# BitBeacon_Type_01.net
KiCad netlist of a schematic drawn in EAGLE
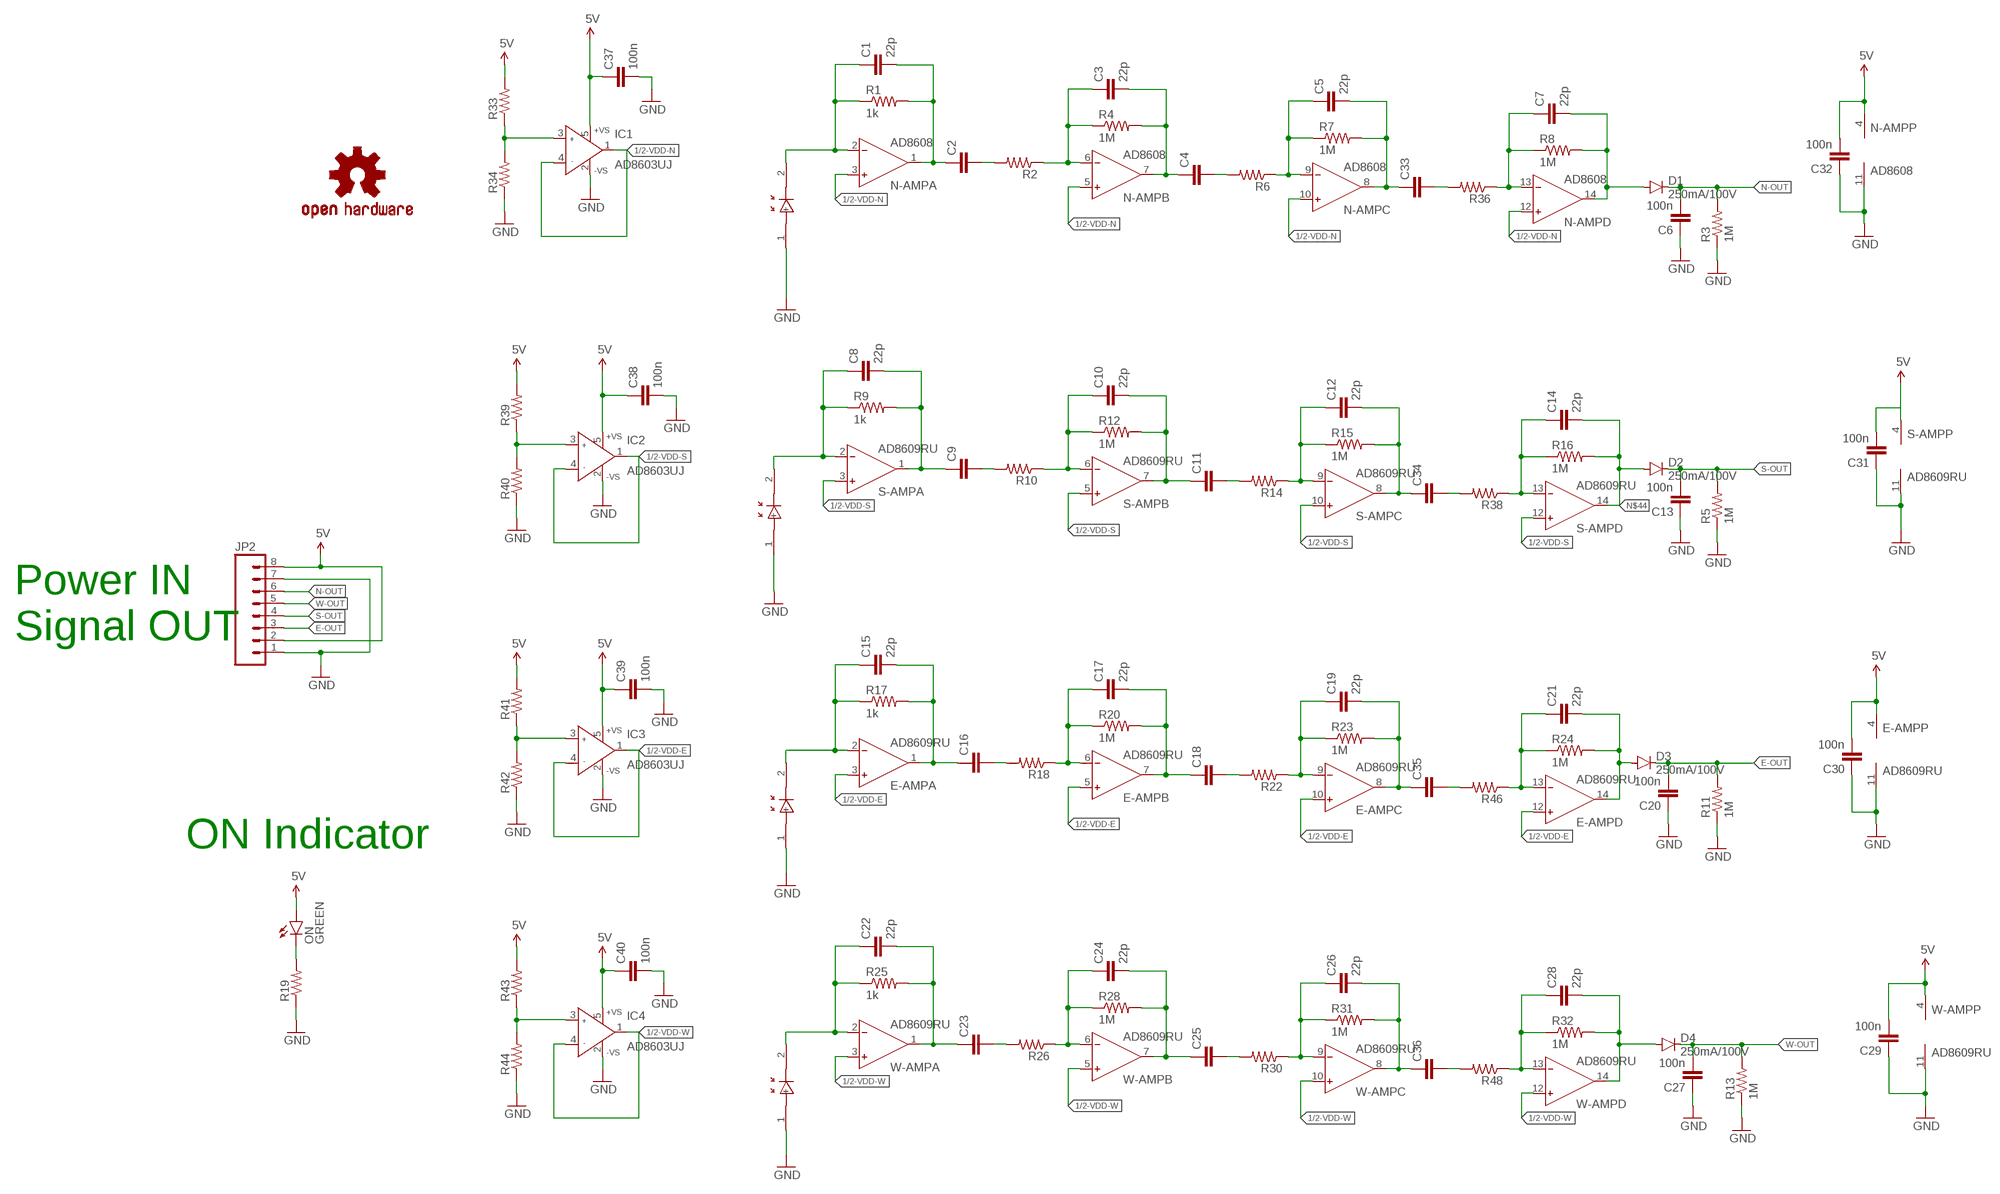
[diagram p0: schematic, sheet 1]

(export (version "E")
  (design (tool "Eeschema 10.0.6"))
  (components
    (comp (ref "C1")
      (value "22p")
      (footprint "eagle-import:C0402")
      (libsource (lib "eagle-import") (part "C-EUC0402"))
    )
    (comp (ref "C2")
      (value "C-EUC0402")
      (footprint "eagle-import:C0402")
      (libsource (lib "eagle-import") (part "C-EUC0402"))
    )
    (comp (ref "C3")
      (value "22p")
      (footprint "eagle-import:C0402")
      (libsource (lib "eagle-import") (part "C-EUC0402"))
    )
    (comp (ref "C4")
      (value "C-EUC0402")
      (footprint "eagle-import:C0402")
      (libsource (lib "eagle-import") (part "C-EUC0402"))
    )
    (comp (ref "C5")
      (value "22p")
      (footprint "eagle-import:C0402")
      (libsource (lib "eagle-import") (part "C-EUC0402"))
    )
    (comp (ref "C6")
      (value "100n")
      (footprint "eagle-import:C0402")
      (libsource (lib "eagle-import") (part "C-EUC0402"))
    )
    (comp (ref "C7")
      (value "22p")
      (footprint "eagle-import:C0402")
      (libsource (lib "eagle-import") (part "C-EUC0402"))
    )
    (comp (ref "C8")
      (value "22p")
      (footprint "eagle-import:C0402")
      (libsource (lib "eagle-import") (part "C-EUC0402"))
    )
    (comp (ref "C9")
      (value "C-EUC0402")
      (footprint "eagle-import:C0402")
      (libsource (lib "eagle-import") (part "C-EUC0402"))
    )
    (comp (ref "C10")
      (value "22p")
      (footprint "eagle-import:C0402")
      (libsource (lib "eagle-import") (part "C-EUC0402"))
    )
    (comp (ref "C11")
      (value "C-EUC0402")
      (footprint "eagle-import:C0402")
      (libsource (lib "eagle-import") (part "C-EUC0402"))
    )
    (comp (ref "C12")
      (value "22p")
      (footprint "eagle-import:C0402")
      (libsource (lib "eagle-import") (part "C-EUC0402"))
    )
    (comp (ref "C13")
      (value "100n")
      (footprint "eagle-import:C0402")
      (libsource (lib "eagle-import") (part "C-EUC0402"))
    )
    (comp (ref "C14")
      (value "22p")
      (footprint "eagle-import:C0402")
      (libsource (lib "eagle-import") (part "C-EUC0402"))
    )
    (comp (ref "C15")
      (value "22p")
      (footprint "eagle-import:C0402")
      (libsource (lib "eagle-import") (part "C-EUC0402"))
    )
    (comp (ref "C16")
      (value "C-EUC0402")
      (footprint "eagle-import:C0402")
      (libsource (lib "eagle-import") (part "C-EUC0402"))
    )
    (comp (ref "C17")
      (value "22p")
      (footprint "eagle-import:C0402")
      (libsource (lib "eagle-import") (part "C-EUC0402"))
    )
    (comp (ref "C18")
      (value "C-EUC0402")
      (footprint "eagle-import:C0402")
      (libsource (lib "eagle-import") (part "C-EUC0402"))
    )
    (comp (ref "C19")
      (value "22p")
      (footprint "eagle-import:C0402")
      (libsource (lib "eagle-import") (part "C-EUC0402"))
    )
    (comp (ref "C20")
      (value "100n")
      (footprint "eagle-import:C0402")
      (libsource (lib "eagle-import") (part "C-EUC0402"))
    )
    (comp (ref "C21")
      (value "22p")
      (footprint "eagle-import:C0402")
      (libsource (lib "eagle-import") (part "C-EUC0402"))
    )
    (comp (ref "C22")
      (value "22p")
      (footprint "eagle-import:C0402")
      (libsource (lib "eagle-import") (part "C-EUC0402"))
    )
    (comp (ref "C23")
      (value "C-EUC0402")
      (footprint "eagle-import:C0402")
      (libsource (lib "eagle-import") (part "C-EUC0402"))
    )
    (comp (ref "C24")
      (value "22p")
      (footprint "eagle-import:C0402")
      (libsource (lib "eagle-import") (part "C-EUC0402"))
    )
    (comp (ref "C25")
      (value "C-EUC0402")
      (footprint "eagle-import:C0402")
      (libsource (lib "eagle-import") (part "C-EUC0402"))
    )
    (comp (ref "C26")
      (value "22p")
      (footprint "eagle-import:C0402")
      (libsource (lib "eagle-import") (part "C-EUC0402"))
    )
    (comp (ref "C27")
      (value "100n")
      (footprint "eagle-import:C0402")
      (libsource (lib "eagle-import") (part "C-EUC0402"))
    )
    (comp (ref "C28")
      (value "22p")
      (footprint "eagle-import:C0402")
      (libsource (lib "eagle-import") (part "C-EUC0402"))
    )
    (comp (ref "C29")
      (value "100n")
      (footprint "eagle-import:C0402")
      (libsource (lib "eagle-import") (part "C-EUC0402"))
    )
    (comp (ref "C30")
      (value "100n")
      (footprint "eagle-import:C0402")
      (libsource (lib "eagle-import") (part "C-EUC0402"))
    )
    (comp (ref "C31")
      (value "100n")
      (footprint "eagle-import:C0402")
      (libsource (lib "eagle-import") (part "C-EUC0402"))
    )
    (comp (ref "C32")
      (value "100n")
      (footprint "eagle-import:C0402")
      (libsource (lib "eagle-import") (part "C-EUC0402"))
    )
    (comp (ref "C33")
      (value "C-EUC0402")
      (footprint "eagle-import:C0402")
      (libsource (lib "eagle-import") (part "C-EUC0402"))
    )
    (comp (ref "C34")
      (value "C-EUC0402")
      (footprint "eagle-import:C0402")
      (libsource (lib "eagle-import") (part "C-EUC0402"))
    )
    (comp (ref "C35")
      (value "C-EUC0402")
      (footprint "eagle-import:C0402")
      (libsource (lib "eagle-import") (part "C-EUC0402"))
    )
    (comp (ref "C36")
      (value "C-EUC0402")
      (footprint "eagle-import:C0402")
      (libsource (lib "eagle-import") (part "C-EUC0402"))
    )
    (comp (ref "C37")
      (value "100n")
      (footprint "eagle-import:C0402")
      (libsource (lib "eagle-import") (part "C-EUC0402"))
    )
    (comp (ref "C38")
      (value "100n")
      (footprint "eagle-import:C0402")
      (libsource (lib "eagle-import") (part "C-EUC0402"))
    )
    (comp (ref "C39")
      (value "100n")
      (footprint "eagle-import:C0402")
      (libsource (lib "eagle-import") (part "C-EUC0402"))
    )
    (comp (ref "C40")
      (value "100n")
      (footprint "eagle-import:C0402")
      (libsource (lib "eagle-import") (part "C-EUC0402"))
    )
    (comp (ref "D1")
      (value "250mA/100V")
      (footprint "eagle-import:SOD-323")
      (libsource (lib "eagle-import") (part "DIODEBAS16"))
    )
    (comp (ref "D2")
      (value "250mA/100V")
      (footprint "eagle-import:SOD-323")
      (libsource (lib "eagle-import") (part "DIODEBAS16"))
    )
    (comp (ref "D3")
      (value "250mA/100V")
      (footprint "eagle-import:SOD-323")
      (libsource (lib "eagle-import") (part "DIODEBAS16"))
    )
    (comp (ref "D4")
      (value "250mA/100V")
      (footprint "eagle-import:SOD-323")
      (libsource (lib "eagle-import") (part "DIODEBAS16"))
    )
    (comp (ref "E-AMP")
      (value "AD8609RU")
      (footprint "eagle-import:TSSOP14")
      (fields (field (name "MF") "ALTERA CORPORATION") (field (name "MPN") "AD8609ARUZ"))
      (libsource (lib "eagle-import") (part "AD8609RU"))
    )
    (comp (ref "E-PD1")
      (value "BPW46")
      (footprint "eagle-import:PIN-PHOTODIODE")
      (libsource (lib "eagle-import") (part "BPW46"))
    )
    (comp (ref "IC1")
      (value "AD8603UJ")
      (footprint "eagle-import:SOT23-5")
      (fields (field (name "MF") "ALTERA CORPORATION") (field (name "MPN") "AD8603AUJZ-REEL7"))
      (libsource (lib "eagle-import") (part "AD8603UJ"))
    )
    (comp (ref "IC2")
      (value "AD8603UJ")
      (footprint "eagle-import:SOT23-5")
      (fields (field (name "MF") "ALTERA CORPORATION") (field (name "MPN") "AD8603AUJZ-REEL7"))
      (libsource (lib "eagle-import") (part "AD8603UJ"))
    )
    (comp (ref "IC3")
      (value "AD8603UJ")
      (footprint "eagle-import:SOT23-5")
      (fields (field (name "MF") "ALTERA CORPORATION") (field (name "MPN") "AD8603AUJZ-REEL7"))
      (libsource (lib "eagle-import") (part "AD8603UJ"))
    )
    (comp (ref "IC4")
      (value "AD8603UJ")
      (footprint "eagle-import:SOT23-5")
      (fields (field (name "MF") "ALTERA CORPORATION") (field (name "MPN") "AD8603AUJZ-REEL7"))
      (libsource (lib "eagle-import") (part "AD8603UJ"))
    )
    (comp (ref "JP2")
      (value "M08NO_SILK")
      (footprint "eagle-import:1X08_PIN1_NO_SILK")
      (libsource (lib "eagle-import") (part "M08NO_SILK"))
    )
    (comp (ref "LOGO1")
      (value "OSHW-LOGOS")
      (footprint "eagle-import:OSHW-LOGO-S")
      (libsource (lib "eagle-import") (part "OSHW-LOGOS"))
    )
    (comp (ref "N-AMP")
      (value "AD8608")
      (footprint "eagle-import:TSSOP14")
      (fields (field (name "MF") "ALTERA CORPORATION") (field (name "MPN") "AD8609ARUZ"))
      (libsource (lib "eagle-import") (part "AD8609RU"))
    )
    (comp (ref "N-PD1")
      (value "BPW46")
      (footprint "eagle-import:PIN-PHOTODIODE")
      (libsource (lib "eagle-import") (part "BPW46"))
    )
    (comp (ref "ON")
      (value "GREEN")
      (footprint "eagle-import:LED-0603")
      (libsource (lib "eagle-import") (part "LED-GREEN0603"))
    )
    (comp (ref "R1")
      (value "1k")
      (footprint "eagle-import:R0402")
      (libsource (lib "eagle-import") (part "R-US_R0402"))
    )
    (comp (ref "R2")
      (value "R-US_R0402")
      (footprint "eagle-import:R0402")
      (libsource (lib "eagle-import") (part "R-US_R0402"))
    )
    (comp (ref "R3")
      (value "1M")
      (footprint "eagle-import:R0402")
      (libsource (lib "eagle-import") (part "R-US_R0402"))
    )
    (comp (ref "R4")
      (value "1M")
      (footprint "eagle-import:R0402")
      (libsource (lib "eagle-import") (part "R-US_R0402"))
    )
    (comp (ref "R5")
      (value "1M")
      (footprint "eagle-import:R0402")
      (libsource (lib "eagle-import") (part "R-US_R0402"))
    )
    (comp (ref "R6")
      (value "R-US_R0402")
      (footprint "eagle-import:R0402")
      (libsource (lib "eagle-import") (part "R-US_R0402"))
    )
    (comp (ref "R7")
      (value "1M")
      (footprint "eagle-import:R0402")
      (libsource (lib "eagle-import") (part "R-US_R0402"))
    )
    (comp (ref "R8")
      (value "1M")
      (footprint "eagle-import:R0402")
      (libsource (lib "eagle-import") (part "R-US_R0402"))
    )
    (comp (ref "R9")
      (value "1k")
      (footprint "eagle-import:R0402")
      (libsource (lib "eagle-import") (part "R-US_R0402"))
    )
    (comp (ref "R10")
      (value "R-US_R0402")
      (footprint "eagle-import:R0402")
      (libsource (lib "eagle-import") (part "R-US_R0402"))
    )
    (comp (ref "R11")
      (value "1M")
      (footprint "eagle-import:R0402")
      (libsource (lib "eagle-import") (part "R-US_R0402"))
    )
    (comp (ref "R12")
      (value "1M")
      (footprint "eagle-import:R0402")
      (libsource (lib "eagle-import") (part "R-US_R0402"))
    )
    (comp (ref "R13")
      (value "1M")
      (footprint "eagle-import:R0402")
      (libsource (lib "eagle-import") (part "R-US_R0402"))
    )
    (comp (ref "R14")
      (value "R-US_R0402")
      (footprint "eagle-import:R0402")
      (libsource (lib "eagle-import") (part "R-US_R0402"))
    )
    (comp (ref "R15")
      (value "1M")
      (footprint "eagle-import:R0402")
      (libsource (lib "eagle-import") (part "R-US_R0402"))
    )
    (comp (ref "R16")
      (value "1M")
      (footprint "eagle-import:R0402")
      (libsource (lib "eagle-import") (part "R-US_R0402"))
    )
    (comp (ref "R17")
      (value "1k")
      (footprint "eagle-import:R0402")
      (libsource (lib "eagle-import") (part "R-US_R0402"))
    )
    (comp (ref "R18")
      (value "R-US_R0402")
      (footprint "eagle-import:R0402")
      (libsource (lib "eagle-import") (part "R-US_R0402"))
    )
    (comp (ref "R19")
      (value "R-US_R0402")
      (footprint "eagle-import:R0402")
      (libsource (lib "eagle-import") (part "R-US_R0402"))
    )
    (comp (ref "R20")
      (value "1M")
      (footprint "eagle-import:R0402")
      (libsource (lib "eagle-import") (part "R-US_R0402"))
    )
    (comp (ref "R22")
      (value "R-US_R0402")
      (footprint "eagle-import:R0402")
      (libsource (lib "eagle-import") (part "R-US_R0402"))
    )
    (comp (ref "R23")
      (value "1M")
      (footprint "eagle-import:R0402")
      (libsource (lib "eagle-import") (part "R-US_R0402"))
    )
    (comp (ref "R24")
      (value "1M")
      (footprint "eagle-import:R0402")
      (libsource (lib "eagle-import") (part "R-US_R0402"))
    )
    (comp (ref "R25")
      (value "1k")
      (footprint "eagle-import:R0402")
      (libsource (lib "eagle-import") (part "R-US_R0402"))
    )
    (comp (ref "R26")
      (value "R-US_R0402")
      (footprint "eagle-import:R0402")
      (libsource (lib "eagle-import") (part "R-US_R0402"))
    )
    (comp (ref "R28")
      (value "1M")
      (footprint "eagle-import:R0402")
      (libsource (lib "eagle-import") (part "R-US_R0402"))
    )
    (comp (ref "R30")
      (value "R-US_R0402")
      (footprint "eagle-import:R0402")
      (libsource (lib "eagle-import") (part "R-US_R0402"))
    )
    (comp (ref "R31")
      (value "1M")
      (footprint "eagle-import:R0402")
      (libsource (lib "eagle-import") (part "R-US_R0402"))
    )
    (comp (ref "R32")
      (value "1M")
      (footprint "eagle-import:R0402")
      (libsource (lib "eagle-import") (part "R-US_R0402"))
    )
    (comp (ref "R33")
      (value "R-US_R0402")
      (footprint "eagle-import:R0402")
      (libsource (lib "eagle-import") (part "R-US_R0402"))
    )
    (comp (ref "R34")
      (value "R-US_R0402")
      (footprint "eagle-import:R0402")
      (libsource (lib "eagle-import") (part "R-US_R0402"))
    )
    (comp (ref "R36")
      (value "R-US_R0402")
      (footprint "eagle-import:R0402")
      (libsource (lib "eagle-import") (part "R-US_R0402"))
    )
    (comp (ref "R38")
      (value "R-US_R0402")
      (footprint "eagle-import:R0402")
      (libsource (lib "eagle-import") (part "R-US_R0402"))
    )
    (comp (ref "R39")
      (value "R-US_R0402")
      (footprint "eagle-import:R0402")
      (libsource (lib "eagle-import") (part "R-US_R0402"))
    )
    (comp (ref "R40")
      (value "R-US_R0402")
      (footprint "eagle-import:R0402")
      (libsource (lib "eagle-import") (part "R-US_R0402"))
    )
    (comp (ref "R41")
      (value "R-US_R0402")
      (footprint "eagle-import:R0402")
      (libsource (lib "eagle-import") (part "R-US_R0402"))
    )
    (comp (ref "R42")
      (value "R-US_R0402")
      (footprint "eagle-import:R0402")
      (libsource (lib "eagle-import") (part "R-US_R0402"))
    )
    (comp (ref "R43")
      (value "R-US_R0402")
      (footprint "eagle-import:R0402")
      (libsource (lib "eagle-import") (part "R-US_R0402"))
    )
    (comp (ref "R44")
      (value "R-US_R0402")
      (footprint "eagle-import:R0402")
      (libsource (lib "eagle-import") (part "R-US_R0402"))
    )
    (comp (ref "R46")
      (value "R-US_R0402")
      (footprint "eagle-import:R0402")
      (libsource (lib "eagle-import") (part "R-US_R0402"))
    )
    (comp (ref "R48")
      (value "R-US_R0402")
      (footprint "eagle-import:R0402")
      (libsource (lib "eagle-import") (part "R-US_R0402"))
    )
    (comp (ref "S-AMP")
      (value "AD8609RU")
      (footprint "eagle-import:TSSOP14")
      (fields (field (name "MF") "ALTERA CORPORATION") (field (name "MPN") "AD8609ARUZ"))
      (libsource (lib "eagle-import") (part "AD8609RU"))
    )
    (comp (ref "S-PD1")
      (value "BPW46")
      (footprint "eagle-import:PIN-PHOTODIODE")
      (libsource (lib "eagle-import") (part "BPW46"))
    )
    (comp (ref "W-AMP")
      (value "AD8609RU")
      (footprint "eagle-import:TSSOP14")
      (fields (field (name "MF") "ALTERA CORPORATION") (field (name "MPN") "AD8609ARUZ"))
      (libsource (lib "eagle-import") (part "AD8609RU"))
    )
    (comp (ref "W-PD1")
      (value "BPW46")
      (footprint "eagle-import:PIN-PHOTODIODE")
      (libsource (lib "eagle-import") (part "BPW46"))
    )
  )
  (nets
    (net (code "1") (name "1{slash}2-VDD-E") (class "Default")
      (node (ref "E-AMP") (pin "10") (pinfunction "IN+_10") (pintype "input"))
      (node (ref "E-AMP") (pin "12") (pinfunction "IN+_12") (pintype "input"))
      (node (ref "E-AMP") (pin "3") (pinfunction "IN+_3") (pintype "input"))
      (node (ref "E-AMP") (pin "5") (pinfunction "IN+_5") (pintype "input"))
      (node (ref "IC3") (pin "1") (pinfunction "OUT_1") (pintype "output"))
      (node (ref "IC3") (pin "4") (pinfunction "IN-_4") (pintype "input"))
    )
    (net (code "2") (name "1{slash}2-VDD-N") (class "Default")
      (node (ref "IC1") (pin "1") (pinfunction "OUT_1") (pintype "output"))
      (node (ref "IC1") (pin "4") (pinfunction "IN-_4") (pintype "input"))
      (node (ref "N-AMP") (pin "10") (pinfunction "IN+_10") (pintype "input"))
      (node (ref "N-AMP") (pin "12") (pinfunction "IN+_12") (pintype "input"))
      (node (ref "N-AMP") (pin "3") (pinfunction "IN+_3") (pintype "input"))
      (node (ref "N-AMP") (pin "5") (pinfunction "IN+_5") (pintype "input"))
    )
    (net (code "3") (name "1{slash}2-VDD-S") (class "Default")
      (node (ref "IC2") (pin "1") (pinfunction "OUT_1") (pintype "output"))
      (node (ref "IC2") (pin "4") (pinfunction "IN-_4") (pintype "input"))
      (node (ref "S-AMP") (pin "10") (pinfunction "IN+_10") (pintype "input"))
      (node (ref "S-AMP") (pin "12") (pinfunction "IN+_12") (pintype "input"))
      (node (ref "S-AMP") (pin "3") (pinfunction "IN+_3") (pintype "input"))
      (node (ref "S-AMP") (pin "5") (pinfunction "IN+_5") (pintype "input"))
    )
    (net (code "4") (name "1{slash}2-VDD-W") (class "Default")
      (node (ref "IC4") (pin "1") (pinfunction "OUT_1") (pintype "output"))
      (node (ref "IC4") (pin "4") (pinfunction "IN-_4") (pintype "input"))
      (node (ref "W-AMP") (pin "10") (pinfunction "IN+_10") (pintype "input"))
      (node (ref "W-AMP") (pin "12") (pinfunction "IN+_12") (pintype "input"))
      (node (ref "W-AMP") (pin "3") (pinfunction "IN+_3") (pintype "input"))
      (node (ref "W-AMP") (pin "5") (pinfunction "IN+_5") (pintype "input"))
    )
    (net (code "5") (name "5V") (class "Default")
      (node (ref "C29") (pin "2") (pinfunction "2_2") (pintype "passive"))
      (node (ref "C30") (pin "2") (pinfunction "2_2") (pintype "passive"))
      (node (ref "C31") (pin "2") (pinfunction "2_2") (pintype "passive"))
      (node (ref "C32") (pin "2") (pinfunction "2_2") (pintype "passive"))
      (node (ref "C37") (pin "1") (pinfunction "1_1") (pintype "passive"))
      (node (ref "C38") (pin "1") (pinfunction "1_1") (pintype "passive"))
      (node (ref "C39") (pin "1") (pinfunction "1_1") (pintype "passive"))
      (node (ref "C40") (pin "1") (pinfunction "1_1") (pintype "passive"))
      (node (ref "E-AMP") (pin "4") (pinfunction "V+_4") (pintype "power_in"))
      (node (ref "IC1") (pin "5") (pinfunction "+VS_5") (pintype "input"))
      (node (ref "IC2") (pin "5") (pinfunction "+VS_5") (pintype "input"))
      (node (ref "IC3") (pin "5") (pinfunction "+VS_5") (pintype "input"))
      (node (ref "IC4") (pin "5") (pinfunction "+VS_5") (pintype "input"))
      (node (ref "JP2") (pin "2") (pinfunction "2_2") (pintype "passive"))
      (node (ref "JP2") (pin "8") (pinfunction "8_8") (pintype "passive"))
      (node (ref "N-AMP") (pin "4") (pinfunction "V+_4") (pintype "power_in"))
      (node (ref "ON") (pin "A") (pinfunction "A_A") (pintype "passive"))
      (node (ref "R33") (pin "2") (pinfunction "2_2") (pintype "passive"))
      (node (ref "R39") (pin "2") (pinfunction "2_2") (pintype "passive"))
      (node (ref "R41") (pin "2") (pinfunction "2_2") (pintype "passive"))
      (node (ref "R43") (pin "2") (pinfunction "2_2") (pintype "passive"))
      (node (ref "S-AMP") (pin "4") (pinfunction "V+_4") (pintype "power_in"))
      (node (ref "W-AMP") (pin "4") (pinfunction "V+_4") (pintype "power_in"))
    )
    (net (code "6") (name "E-OUT") (class "Default")
      (node (ref "C20") (pin "2") (pinfunction "2_2") (pintype "passive"))
      (node (ref "D3") (pin "C") (pinfunction "C_C") (pintype "passive"))
      (node (ref "JP2") (pin "3") (pinfunction "3_3") (pintype "passive"))
      (node (ref "R11") (pin "2") (pinfunction "2_2") (pintype "passive"))
    )
    (net (code "7") (name "GND") (class "Default")
      (node (ref "C13") (pin "1") (pinfunction "1_1") (pintype "passive"))
      (node (ref "C20") (pin "1") (pinfunction "1_1") (pintype "passive"))
      (node (ref "C27") (pin "1") (pinfunction "1_1") (pintype "passive"))
      (node (ref "C29") (pin "1") (pinfunction "1_1") (pintype "passive"))
      (node (ref "C30") (pin "1") (pinfunction "1_1") (pintype "passive"))
      (node (ref "C31") (pin "1") (pinfunction "1_1") (pintype "passive"))
      (node (ref "C32") (pin "1") (pinfunction "1_1") (pintype "passive"))
      (node (ref "C37") (pin "2") (pinfunction "2_2") (pintype "passive"))
      (node (ref "C38") (pin "2") (pinfunction "2_2") (pintype "passive"))
      (node (ref "C39") (pin "2") (pinfunction "2_2") (pintype "passive"))
      (node (ref "C40") (pin "2") (pinfunction "2_2") (pintype "passive"))
      (node (ref "C6") (pin "1") (pinfunction "1_1") (pintype "passive"))
      (node (ref "E-AMP") (pin "11") (pinfunction "V-_11") (pintype "power_in"))
      (node (ref "E-PD1") (pin "1") (pinfunction "+_1") (pintype "bidirectional"))
      (node (ref "IC1") (pin "2") (pinfunction "-VS_2") (pintype "input"))
      (node (ref "IC2") (pin "2") (pinfunction "-VS_2") (pintype "input"))
      (node (ref "IC3") (pin "2") (pinfunction "-VS_2") (pintype "input"))
      (node (ref "IC4") (pin "2") (pinfunction "-VS_2") (pintype "input"))
      (node (ref "JP2") (pin "1") (pinfunction "1_1") (pintype "passive"))
      (node (ref "JP2") (pin "7") (pinfunction "7_7") (pintype "passive"))
      (node (ref "N-AMP") (pin "11") (pinfunction "V-_11") (pintype "power_in"))
      (node (ref "N-PD1") (pin "1") (pinfunction "+_1") (pintype "bidirectional"))
      (node (ref "R11") (pin "1") (pinfunction "1_1") (pintype "passive"))
      (node (ref "R13") (pin "1") (pinfunction "1_1") (pintype "passive"))
      (node (ref "R19") (pin "1") (pinfunction "1_1") (pintype "passive"))
      (node (ref "R3") (pin "1") (pinfunction "1_1") (pintype "passive"))
      (node (ref "R34") (pin "1") (pinfunction "1_1") (pintype "passive"))
      (node (ref "R40") (pin "1") (pinfunction "1_1") (pintype "passive"))
      (node (ref "R42") (pin "1") (pinfunction "1_1") (pintype "passive"))
      (node (ref "R44") (pin "1") (pinfunction "1_1") (pintype "passive"))
      (node (ref "R5") (pin "1") (pinfunction "1_1") (pintype "passive"))
      (node (ref "S-AMP") (pin "11") (pinfunction "V-_11") (pintype "power_in"))
      (node (ref "S-PD1") (pin "1") (pinfunction "+_1") (pintype "bidirectional"))
      (node (ref "W-AMP") (pin "11") (pinfunction "V-_11") (pintype "power_in"))
      (node (ref "W-PD1") (pin "1") (pinfunction "+_1") (pintype "bidirectional"))
    )
    (net (code "8") (name "N$44") (class "Default")
      (node (ref "C14") (pin "2") (pinfunction "2_2") (pintype "passive"))
      (node (ref "D2") (pin "A") (pinfunction "A_A") (pintype "passive"))
      (node (ref "R16") (pin "2") (pinfunction "2_2") (pintype "passive"))
      (node (ref "S-AMP") (pin "14") (pinfunction "OUT_14") (pintype "output"))
    )
    (net (code "9") (name "N-OUT") (class "Default")
      (node (ref "C6") (pin "2") (pinfunction "2_2") (pintype "passive"))
      (node (ref "D1") (pin "C") (pinfunction "C_C") (pintype "passive"))
      (node (ref "JP2") (pin "6") (pinfunction "6_6") (pintype "passive"))
      (node (ref "R3") (pin "2") (pinfunction "2_2") (pintype "passive"))
    )
    (net (code "10") (name "Net-(C2-Pad2)") (class "Default")
      (node (ref "C2") (pin "2") (pinfunction "2_2") (pintype "passive"))
      (node (ref "R2") (pin "2") (pinfunction "2_2") (pintype "passive"))
    )
    (net (code "11") (name "Net-(C4-Pad2)") (class "Default")
      (node (ref "C4") (pin "2") (pinfunction "2_2") (pintype "passive"))
      (node (ref "R6") (pin "2") (pinfunction "2_2") (pintype "passive"))
    )
    (net (code "12") (name "Net-(C9-Pad2)") (class "Default")
      (node (ref "C9") (pin "2") (pinfunction "2_2") (pintype "passive"))
      (node (ref "R10") (pin "2") (pinfunction "2_2") (pintype "passive"))
    )
    (net (code "13") (name "Net-(C11-Pad2)") (class "Default")
      (node (ref "C11") (pin "2") (pinfunction "2_2") (pintype "passive"))
      (node (ref "R14") (pin "2") (pinfunction "2_2") (pintype "passive"))
    )
    (net (code "14") (name "Net-(C16-Pad2)") (class "Default")
      (node (ref "C16") (pin "2") (pinfunction "2_2") (pintype "passive"))
      (node (ref "R18") (pin "2") (pinfunction "2_2") (pintype "passive"))
    )
    (net (code "15") (name "Net-(C18-Pad2)") (class "Default")
      (node (ref "C18") (pin "2") (pinfunction "2_2") (pintype "passive"))
      (node (ref "R22") (pin "2") (pinfunction "2_2") (pintype "passive"))
    )
    (net (code "16") (name "Net-(C23-Pad2)") (class "Default")
      (node (ref "C23") (pin "2") (pinfunction "2_2") (pintype "passive"))
      (node (ref "R26") (pin "2") (pinfunction "2_2") (pintype "passive"))
    )
    (net (code "17") (name "Net-(C25-Pad2)") (class "Default")
      (node (ref "C25") (pin "2") (pinfunction "2_2") (pintype "passive"))
      (node (ref "R30") (pin "2") (pinfunction "2_2") (pintype "passive"))
    )
    (net (code "18") (name "Net-(C33-Pad2)") (class "Default")
      (node (ref "C33") (pin "2") (pinfunction "2_2") (pintype "passive"))
      (node (ref "R36") (pin "2") (pinfunction "2_2") (pintype "passive"))
    )
    (net (code "19") (name "Net-(C34-Pad2)") (class "Default")
      (node (ref "C34") (pin "2") (pinfunction "2_2") (pintype "passive"))
      (node (ref "R38") (pin "2") (pinfunction "2_2") (pintype "passive"))
    )
    (net (code "20") (name "Net-(C35-Pad2)") (class "Default")
      (node (ref "C35") (pin "2") (pinfunction "2_2") (pintype "passive"))
      (node (ref "R46") (pin "2") (pinfunction "2_2") (pintype "passive"))
    )
    (net (code "21") (name "Net-(C36-Pad2)") (class "Default")
      (node (ref "C36") (pin "2") (pinfunction "2_2") (pintype "passive"))
      (node (ref "R48") (pin "2") (pinfunction "2_2") (pintype "passive"))
    )
    (net (code "22") (name "Net-(E-AMPA-IN-)") (class "Default")
      (node (ref "C15") (pin "1") (pinfunction "1_1") (pintype "passive"))
      (node (ref "E-AMP") (pin "2") (pinfunction "IN-_2") (pintype "input"))
      (node (ref "E-PD1") (pin "2") (pinfunction "-_2") (pintype "bidirectional"))
      (node (ref "R17") (pin "1") (pinfunction "1_1") (pintype "passive"))
    )
    (net (code "23") (name "Net-(E-AMPA-OUT)") (class "Default")
      (node (ref "C15") (pin "2") (pinfunction "2_2") (pintype "passive"))
      (node (ref "C16") (pin "1") (pinfunction "1_1") (pintype "passive"))
      (node (ref "E-AMP") (pin "1") (pinfunction "OUT_1") (pintype "output"))
      (node (ref "R17") (pin "2") (pinfunction "2_2") (pintype "passive"))
    )
    (net (code "24") (name "Net-(E-AMPB-IN-)") (class "Default")
      (node (ref "C17") (pin "1") (pinfunction "1_1") (pintype "passive"))
      (node (ref "E-AMP") (pin "6") (pinfunction "IN-_6") (pintype "input"))
      (node (ref "R18") (pin "1") (pinfunction "1_1") (pintype "passive"))
      (node (ref "R20") (pin "1") (pinfunction "1_1") (pintype "passive"))
    )
    (net (code "25") (name "Net-(E-AMPB-OUT)") (class "Default")
      (node (ref "C17") (pin "2") (pinfunction "2_2") (pintype "passive"))
      (node (ref "C18") (pin "1") (pinfunction "1_1") (pintype "passive"))
      (node (ref "E-AMP") (pin "7") (pinfunction "OUT_7") (pintype "output"))
      (node (ref "R20") (pin "2") (pinfunction "2_2") (pintype "passive"))
    )
    (net (code "26") (name "Net-(E-AMPC-IN-)") (class "Default")
      (node (ref "C19") (pin "1") (pinfunction "1_1") (pintype "passive"))
      (node (ref "E-AMP") (pin "9") (pinfunction "IN-_9") (pintype "input"))
      (node (ref "R22") (pin "1") (pinfunction "1_1") (pintype "passive"))
      (node (ref "R23") (pin "1") (pinfunction "1_1") (pintype "passive"))
    )
    (net (code "27") (name "Net-(E-AMPC-OUT)") (class "Default")
      (node (ref "C19") (pin "2") (pinfunction "2_2") (pintype "passive"))
      (node (ref "C35") (pin "1") (pinfunction "1_1") (pintype "passive"))
      (node (ref "E-AMP") (pin "8") (pinfunction "OUT_8") (pintype "output"))
      (node (ref "R23") (pin "2") (pinfunction "2_2") (pintype "passive"))
    )
    (net (code "28") (name "Net-(E-AMPD-IN-)") (class "Default")
      (node (ref "C21") (pin "1") (pinfunction "1_1") (pintype "passive"))
      (node (ref "E-AMP") (pin "13") (pinfunction "IN-_13") (pintype "input"))
      (node (ref "R24") (pin "1") (pinfunction "1_1") (pintype "passive"))
      (node (ref "R46") (pin "1") (pinfunction "1_1") (pintype "passive"))
    )
    (net (code "29") (name "Net-(E-AMPD-OUT)") (class "Default")
      (node (ref "C21") (pin "2") (pinfunction "2_2") (pintype "passive"))
      (node (ref "D3") (pin "A") (pinfunction "A_A") (pintype "passive"))
      (node (ref "E-AMP") (pin "14") (pinfunction "OUT_14") (pintype "output"))
      (node (ref "R24") (pin "2") (pinfunction "2_2") (pintype "passive"))
    )
    (net (code "30") (name "Net-(IC1-IN+)") (class "Default")
      (node (ref "IC1") (pin "3") (pinfunction "IN+_3") (pintype "input"))
      (node (ref "R33") (pin "1") (pinfunction "1_1") (pintype "passive"))
      (node (ref "R34") (pin "2") (pinfunction "2_2") (pintype "passive"))
    )
    (net (code "31") (name "Net-(IC2-IN+)") (class "Default")
      (node (ref "IC2") (pin "3") (pinfunction "IN+_3") (pintype "input"))
      (node (ref "R39") (pin "1") (pinfunction "1_1") (pintype "passive"))
      (node (ref "R40") (pin "2") (pinfunction "2_2") (pintype "passive"))
    )
    (net (code "32") (name "Net-(IC3-IN+)") (class "Default")
      (node (ref "IC3") (pin "3") (pinfunction "IN+_3") (pintype "input"))
      (node (ref "R41") (pin "1") (pinfunction "1_1") (pintype "passive"))
      (node (ref "R42") (pin "2") (pinfunction "2_2") (pintype "passive"))
    )
    (net (code "33") (name "Net-(IC4-IN+)") (class "Default")
      (node (ref "IC4") (pin "3") (pinfunction "IN+_3") (pintype "input"))
      (node (ref "R43") (pin "1") (pinfunction "1_1") (pintype "passive"))
      (node (ref "R44") (pin "2") (pinfunction "2_2") (pintype "passive"))
    )
    (net (code "34") (name "Net-(N-AMPA-IN-)") (class "Default")
      (node (ref "C1") (pin "1") (pinfunction "1_1") (pintype "passive"))
      (node (ref "N-AMP") (pin "2") (pinfunction "IN-_2") (pintype "input"))
      (node (ref "N-PD1") (pin "2") (pinfunction "-_2") (pintype "bidirectional"))
      (node (ref "R1") (pin "1") (pinfunction "1_1") (pintype "passive"))
    )
    (net (code "35") (name "Net-(N-AMPA-OUT)") (class "Default")
      (node (ref "C1") (pin "2") (pinfunction "2_2") (pintype "passive"))
      (node (ref "C2") (pin "1") (pinfunction "1_1") (pintype "passive"))
      (node (ref "N-AMP") (pin "1") (pinfunction "OUT_1") (pintype "output"))
      (node (ref "R1") (pin "2") (pinfunction "2_2") (pintype "passive"))
    )
    (net (code "36") (name "Net-(N-AMPB-IN-)") (class "Default")
      (node (ref "C3") (pin "1") (pinfunction "1_1") (pintype "passive"))
      (node (ref "N-AMP") (pin "6") (pinfunction "IN-_6") (pintype "input"))
      (node (ref "R2") (pin "1") (pinfunction "1_1") (pintype "passive"))
      (node (ref "R4") (pin "1") (pinfunction "1_1") (pintype "passive"))
    )
    (net (code "37") (name "Net-(N-AMPB-OUT)") (class "Default")
      (node (ref "C3") (pin "2") (pinfunction "2_2") (pintype "passive"))
      (node (ref "C4") (pin "1") (pinfunction "1_1") (pintype "passive"))
      (node (ref "N-AMP") (pin "7") (pinfunction "OUT_7") (pintype "output"))
      (node (ref "R4") (pin "2") (pinfunction "2_2") (pintype "passive"))
    )
    (net (code "38") (name "Net-(N-AMPC-IN-)") (class "Default")
      (node (ref "C5") (pin "1") (pinfunction "1_1") (pintype "passive"))
      (node (ref "N-AMP") (pin "9") (pinfunction "IN-_9") (pintype "input"))
      (node (ref "R6") (pin "1") (pinfunction "1_1") (pintype "passive"))
      (node (ref "R7") (pin "1") (pinfunction "1_1") (pintype "passive"))
    )
    (net (code "39") (name "Net-(N-AMPC-OUT)") (class "Default")
      (node (ref "C33") (pin "1") (pinfunction "1_1") (pintype "passive"))
      (node (ref "C5") (pin "2") (pinfunction "2_2") (pintype "passive"))
      (node (ref "N-AMP") (pin "8") (pinfunction "OUT_8") (pintype "output"))
      (node (ref "R7") (pin "2") (pinfunction "2_2") (pintype "passive"))
    )
    (net (code "40") (name "Net-(N-AMPD-IN-)") (class "Default")
      (node (ref "C7") (pin "1") (pinfunction "1_1") (pintype "passive"))
      (node (ref "N-AMP") (pin "13") (pinfunction "IN-_13") (pintype "input"))
      (node (ref "R36") (pin "1") (pinfunction "1_1") (pintype "passive"))
      (node (ref "R8") (pin "1") (pinfunction "1_1") (pintype "passive"))
    )
    (net (code "41") (name "Net-(N-AMPD-OUT)") (class "Default")
      (node (ref "C7") (pin "2") (pinfunction "2_2") (pintype "passive"))
      (node (ref "D1") (pin "A") (pinfunction "A_A") (pintype "passive"))
      (node (ref "N-AMP") (pin "14") (pinfunction "OUT_14") (pintype "output"))
      (node (ref "R8") (pin "2") (pinfunction "2_2") (pintype "passive"))
    )
    (net (code "42") (name "Net-(ON-PadC)") (class "Default")
      (node (ref "ON") (pin "C") (pinfunction "C_C") (pintype "passive"))
      (node (ref "R19") (pin "2") (pinfunction "2_2") (pintype "passive"))
    )
    (net (code "43") (name "Net-(S-AMPA-IN-)") (class "Default")
      (node (ref "C8") (pin "1") (pinfunction "1_1") (pintype "passive"))
      (node (ref "R9") (pin "1") (pinfunction "1_1") (pintype "passive"))
      (node (ref "S-AMP") (pin "2") (pinfunction "IN-_2") (pintype "input"))
      (node (ref "S-PD1") (pin "2") (pinfunction "-_2") (pintype "bidirectional"))
    )
    (net (code "44") (name "Net-(S-AMPA-OUT)") (class "Default")
      (node (ref "C8") (pin "2") (pinfunction "2_2") (pintype "passive"))
      (node (ref "C9") (pin "1") (pinfunction "1_1") (pintype "passive"))
      (node (ref "R9") (pin "2") (pinfunction "2_2") (pintype "passive"))
      (node (ref "S-AMP") (pin "1") (pinfunction "OUT_1") (pintype "output"))
    )
    (net (code "45") (name "Net-(S-AMPB-IN-)") (class "Default")
      (node (ref "C10") (pin "1") (pinfunction "1_1") (pintype "passive"))
      (node (ref "R10") (pin "1") (pinfunction "1_1") (pintype "passive"))
      (node (ref "R12") (pin "1") (pinfunction "1_1") (pintype "passive"))
      (node (ref "S-AMP") (pin "6") (pinfunction "IN-_6") (pintype "input"))
    )
    (net (code "46") (name "Net-(S-AMPB-OUT)") (class "Default")
      (node (ref "C10") (pin "2") (pinfunction "2_2") (pintype "passive"))
      (node (ref "C11") (pin "1") (pinfunction "1_1") (pintype "passive"))
      (node (ref "R12") (pin "2") (pinfunction "2_2") (pintype "passive"))
      (node (ref "S-AMP") (pin "7") (pinfunction "OUT_7") (pintype "output"))
    )
    (net (code "47") (name "Net-(S-AMPC-IN-)") (class "Default")
      (node (ref "C12") (pin "1") (pinfunction "1_1") (pintype "passive"))
      (node (ref "R14") (pin "1") (pinfunction "1_1") (pintype "passive"))
      (node (ref "R15") (pin "1") (pinfunction "1_1") (pintype "passive"))
      (node (ref "S-AMP") (pin "9") (pinfunction "IN-_9") (pintype "input"))
    )
    (net (code "48") (name "Net-(S-AMPC-OUT)") (class "Default")
      (node (ref "C12") (pin "2") (pinfunction "2_2") (pintype "passive"))
      (node (ref "C34") (pin "1") (pinfunction "1_1") (pintype "passive"))
      (node (ref "R15") (pin "2") (pinfunction "2_2") (pintype "passive"))
      (node (ref "S-AMP") (pin "8") (pinfunction "OUT_8") (pintype "output"))
    )
    (net (code "49") (name "Net-(S-AMPD-IN-)") (class "Default")
      (node (ref "C14") (pin "1") (pinfunction "1_1") (pintype "passive"))
      (node (ref "R16") (pin "1") (pinfunction "1_1") (pintype "passive"))
      (node (ref "R38") (pin "1") (pinfunction "1_1") (pintype "passive"))
      (node (ref "S-AMP") (pin "13") (pinfunction "IN-_13") (pintype "input"))
    )
    (net (code "50") (name "Net-(W-AMPA-IN-)") (class "Default")
      (node (ref "C22") (pin "1") (pinfunction "1_1") (pintype "passive"))
      (node (ref "R25") (pin "1") (pinfunction "1_1") (pintype "passive"))
      (node (ref "W-AMP") (pin "2") (pinfunction "IN-_2") (pintype "input"))
      (node (ref "W-PD1") (pin "2") (pinfunction "-_2") (pintype "bidirectional"))
    )
    (net (code "51") (name "Net-(W-AMPA-OUT)") (class "Default")
      (node (ref "C22") (pin "2") (pinfunction "2_2") (pintype "passive"))
      (node (ref "C23") (pin "1") (pinfunction "1_1") (pintype "passive"))
      (node (ref "R25") (pin "2") (pinfunction "2_2") (pintype "passive"))
      (node (ref "W-AMP") (pin "1") (pinfunction "OUT_1") (pintype "output"))
    )
    (net (code "52") (name "Net-(W-AMPB-IN-)") (class "Default")
      (node (ref "C24") (pin "1") (pinfunction "1_1") (pintype "passive"))
      (node (ref "R26") (pin "1") (pinfunction "1_1") (pintype "passive"))
      (node (ref "R28") (pin "1") (pinfunction "1_1") (pintype "passive"))
      (node (ref "W-AMP") (pin "6") (pinfunction "IN-_6") (pintype "input"))
    )
    (net (code "53") (name "Net-(W-AMPB-OUT)") (class "Default")
      (node (ref "C24") (pin "2") (pinfunction "2_2") (pintype "passive"))
      (node (ref "C25") (pin "1") (pinfunction "1_1") (pintype "passive"))
      (node (ref "R28") (pin "2") (pinfunction "2_2") (pintype "passive"))
      (node (ref "W-AMP") (pin "7") (pinfunction "OUT_7") (pintype "output"))
    )
    (net (code "54") (name "Net-(W-AMPC-IN-)") (class "Default")
      (node (ref "C26") (pin "1") (pinfunction "1_1") (pintype "passive"))
      (node (ref "R30") (pin "1") (pinfunction "1_1") (pintype "passive"))
      (node (ref "R31") (pin "1") (pinfunction "1_1") (pintype "passive"))
      (node (ref "W-AMP") (pin "9") (pinfunction "IN-_9") (pintype "input"))
    )
    (net (code "55") (name "Net-(W-AMPC-OUT)") (class "Default")
      (node (ref "C26") (pin "2") (pinfunction "2_2") (pintype "passive"))
      (node (ref "C36") (pin "1") (pinfunction "1_1") (pintype "passive"))
      (node (ref "R31") (pin "2") (pinfunction "2_2") (pintype "passive"))
      (node (ref "W-AMP") (pin "8") (pinfunction "OUT_8") (pintype "output"))
    )
    (net (code "56") (name "Net-(W-AMPD-IN-)") (class "Default")
      (node (ref "C28") (pin "1") (pinfunction "1_1") (pintype "passive"))
      (node (ref "R32") (pin "1") (pinfunction "1_1") (pintype "passive"))
      (node (ref "R48") (pin "1") (pinfunction "1_1") (pintype "passive"))
      (node (ref "W-AMP") (pin "13") (pinfunction "IN-_13") (pintype "input"))
    )
    (net (code "57") (name "Net-(W-AMPD-OUT)") (class "Default")
      (node (ref "C28") (pin "2") (pinfunction "2_2") (pintype "passive"))
      (node (ref "D4") (pin "A") (pinfunction "A_A") (pintype "passive"))
      (node (ref "R32") (pin "2") (pinfunction "2_2") (pintype "passive"))
      (node (ref "W-AMP") (pin "14") (pinfunction "OUT_14") (pintype "output"))
    )
    (net (code "58") (name "S-OUT") (class "Default")
      (node (ref "C13") (pin "2") (pinfunction "2_2") (pintype "passive"))
      (node (ref "D2") (pin "C") (pinfunction "C_C") (pintype "passive"))
      (node (ref "JP2") (pin "4") (pinfunction "4_4") (pintype "passive"))
      (node (ref "R5") (pin "2") (pinfunction "2_2") (pintype "passive"))
    )
    (net (code "59") (name "W-OUT") (class "Default")
      (node (ref "C27") (pin "2") (pinfunction "2_2") (pintype "passive"))
      (node (ref "D4") (pin "C") (pinfunction "C_C") (pintype "passive"))
      (node (ref "JP2") (pin "5") (pinfunction "5_5") (pintype "passive"))
      (node (ref "R13") (pin "2") (pinfunction "2_2") (pintype "passive"))
    )
  )
)
